# vitor-project.net
KiCad netlist of a schematic drawn in Altium Designer
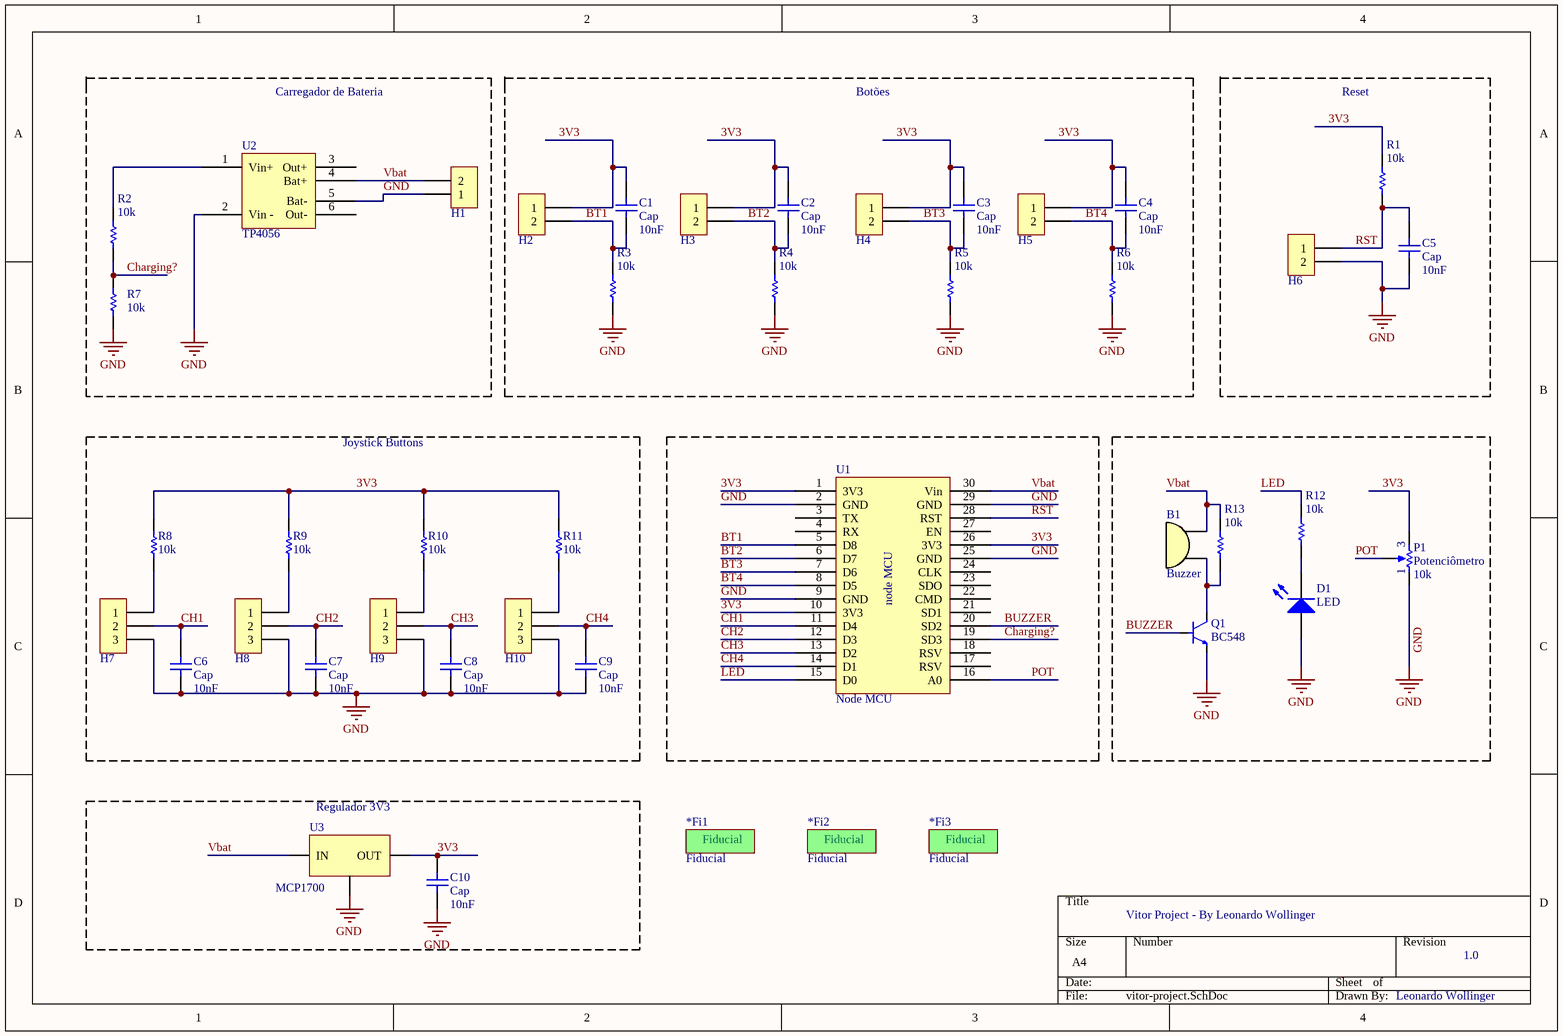
[diagram p0: vitor-project.SchDoc]

(export (version "E")
  (design (tool "Eeschema 10.0.6"))
  (components
    (comp (ref "*Fi1")
      (value "Fiducial")
      (footprint "Fiducial")
      (description "Fiduciais para montagem em pick n' place")
      (libsource (lib "pako") (part "Fiducial"))
    )
    (comp (ref "*Fi2")
      (value "Fiducial")
      (footprint "Fiducial")
      (description "Fiduciais para montagem em pick n' place")
      (libsource (lib "pako") (part "Fiducial"))
    )
    (comp (ref "*Fi3")
      (value "Fiducial")
      (footprint "Fiducial")
      (description "Fiduciais para montagem em pick n' place")
      (libsource (lib "pako") (part "Fiducial"))
    )
    (comp (ref "B1") (value "Buzzer") (footprint "Buzzer") (libsource (lib "pako") (part "Buzzer")))
    (comp (ref "C1")
      (value "Cap")
      (footprint "Cap 100")
      (fields (field (name "VALOR") "10nF"))
      (libsource (lib "pako") (part "Cap"))
    )
    (comp (ref "C2")
      (value "Cap")
      (footprint "Cap 100")
      (fields (field (name "VALOR") "10nF"))
      (libsource (lib "pako") (part "Cap"))
    )
    (comp (ref "C3")
      (value "Cap")
      (footprint "Cap 100")
      (fields (field (name "VALOR") "10nF"))
      (libsource (lib "pako") (part "Cap"))
    )
    (comp (ref "C4")
      (value "Cap")
      (footprint "Cap 100")
      (fields (field (name "VALOR") "10nF"))
      (libsource (lib "pako") (part "Cap"))
    )
    (comp (ref "C5")
      (value "Cap")
      (footprint "Cap 100")
      (fields (field (name "VALOR") "10nF"))
      (libsource (lib "pako") (part "Cap"))
    )
    (comp (ref "C6")
      (value "Cap")
      (footprint "Cap 100")
      (fields (field (name "VALOR") "10nF"))
      (libsource (lib "pako") (part "Cap"))
    )
    (comp (ref "C7")
      (value "Cap")
      (footprint "Cap 100")
      (fields (field (name "VALOR") "10nF"))
      (libsource (lib "pako") (part "Cap"))
    )
    (comp (ref "C8")
      (value "Cap")
      (footprint "Cap 100")
      (fields (field (name "VALOR") "10nF"))
      (libsource (lib "pako") (part "Cap"))
    )
    (comp (ref "C9")
      (value "Cap")
      (footprint "Cap 100")
      (fields (field (name "VALOR") "10nF"))
      (libsource (lib "pako") (part "Cap"))
    )
    (comp (ref "C10")
      (value "Cap")
      (footprint "Cap 100")
      (fields (field (name "VALOR") "10nF"))
      (libsource (lib "pako") (part "Cap"))
    )
    (comp (ref "D1") (value "LED") (footprint "LED 5mm") (libsource (lib "pako") (part "LED")))
    (comp (ref "H1")
      (value "Header 2x1")
      (footprint "Header 2x1")
      (libsource (lib "pako") (part "Header 2x1"))
    )
    (comp (ref "H2") (value "Header 2x1") (footprint "Header 2x1") (libsource (lib "") (part "Header 2x1_1")))
    (comp (ref "H3") (value "Header 2x1") (footprint "Header 2x1") (libsource (lib "") (part "Header 2x1_1")))
    (comp (ref "H4") (value "Header 2x1") (footprint "Header 2x1") (libsource (lib "") (part "Header 2x1_1")))
    (comp (ref "H5") (value "Header 2x1") (footprint "Header 2x1") (libsource (lib "") (part "Header 2x1_1")))
    (comp (ref "H6") (value "Header 2x1") (footprint "Header 2x1") (libsource (lib "") (part "Header 2x1_1")))
    (comp (ref "H7")
      (value "Header 3x1")
      (footprint "Header 3x1")
      (libsource (lib "pako") (part "Header 3x1"))
    )
    (comp (ref "H8")
      (value "Header 3x1")
      (footprint "Header 3x1")
      (libsource (lib "pako") (part "Header 3x1"))
    )
    (comp (ref "H9")
      (value "Header 3x1")
      (footprint "Header 3x1")
      (libsource (lib "pako") (part "Header 3x1"))
    )
    (comp (ref "H10")
      (value "Header 3x1")
      (footprint "Header 3x1")
      (libsource (lib "pako") (part "Header 3x1"))
    )
    (comp (ref "P1")
      (value "Potenciômetro")
      (footprint "Potenciometro Vertical")
      (fields (field (name "VALOR") "10k"))
      (libsource (lib "pako") (part "Potenciômetro"))
    )
    (comp (ref "Q1")
      (value "BC548")
      (footprint "TO-92")
      (description "Transistor NPN")
      (libsource (lib "pako") (part "BC548"))
    )
    (comp (ref "R1")
      (value "Resistor")
      (footprint "Resistor 1/4W")
      (fields (field (name "VALOR") "10k"))
      (libsource (lib "pako") (part "Resistor"))
    )
    (comp (ref "R2")
      (value "Resistor")
      (footprint "Resistor 1/4W")
      (fields (field (name "VALOR") "10k"))
      (libsource (lib "pako") (part "Resistor"))
    )
    (comp (ref "R3")
      (value "Resistor")
      (footprint "Resistor 1/4W")
      (fields (field (name "VALOR") "10k"))
      (libsource (lib "pako") (part "Resistor"))
    )
    (comp (ref "R4")
      (value "Resistor")
      (footprint "Resistor 1/4W")
      (fields (field (name "VALOR") "10k"))
      (libsource (lib "pako") (part "Resistor"))
    )
    (comp (ref "R5")
      (value "Resistor")
      (footprint "Resistor 1/4W")
      (fields (field (name "VALOR") "10k"))
      (libsource (lib "pako") (part "Resistor"))
    )
    (comp (ref "R6")
      (value "Resistor")
      (footprint "Resistor 1/4W")
      (fields (field (name "VALOR") "10k"))
      (libsource (lib "pako") (part "Resistor"))
    )
    (comp (ref "R7")
      (value "Resistor")
      (footprint "Resistor 1/4W")
      (fields (field (name "VALOR") "10k"))
      (libsource (lib "pako") (part "Resistor"))
    )
    (comp (ref "R8")
      (value "Resistor")
      (footprint "Resistor 1/4W")
      (fields (field (name "VALOR") "10k"))
      (libsource (lib "pako") (part "Resistor"))
    )
    (comp (ref "R9")
      (value "Resistor")
      (footprint "Resistor 1/4W")
      (fields (field (name "VALOR") "10k"))
      (libsource (lib "pako") (part "Resistor"))
    )
    (comp (ref "R10")
      (value "Resistor")
      (footprint "Resistor 1/4W")
      (fields (field (name "VALOR") "10k"))
      (libsource (lib "pako") (part "Resistor"))
    )
    (comp (ref "R11")
      (value "Resistor")
      (footprint "Resistor 1/4W")
      (fields (field (name "VALOR") "10k"))
      (libsource (lib "pako") (part "Resistor"))
    )
    (comp (ref "R12")
      (value "Resistor")
      (footprint "Resistor 1/4W")
      (fields (field (name "VALOR") "10k"))
      (libsource (lib "pako") (part "Resistor"))
    )
    (comp (ref "R13")
      (value "Resistor")
      (footprint "Resistor 1/4W")
      (fields (field (name "VALOR") "10k"))
      (libsource (lib "pako") (part "Resistor"))
    )
    (comp (ref "U1")
      (value "Node MCU")
      (footprint "pako:Node MCU")
      (libsource (lib "pako") (part "Node MCU"))
    )
    (comp (ref "U2") (value "TP4056") (footprint "pako:TP4056") (libsource (lib "pako") (part "TP4056")))
    (comp (ref "U3")
      (value "MCP1700")
      (footprint "TO-92")
      (description "LDO Voltage Regulator")
      (libsource (lib "pako") (part "MCP1700"))
    )
  )
  (nets
    (net (code "1") (name "/3V3") (class "Default")
      (node (ref "C1") (pin "1") (pintype "passive"))
      (node (ref "C10") (pin "1") (pintype "passive"))
      (node (ref "C2") (pin "1") (pintype "passive"))
      (node (ref "C3") (pin "1") (pintype "passive"))
      (node (ref "C4") (pin "1") (pintype "passive"))
      (node (ref "H2") (pin "1") (pinfunction "1_1") (pintype "passive"))
      (node (ref "H3") (pin "1") (pinfunction "1_1") (pintype "passive"))
      (node (ref "H4") (pin "1") (pinfunction "1_1") (pintype "passive"))
      (node (ref "H5") (pin "1") (pinfunction "1_1") (pintype "passive"))
      (node (ref "P1") (pin "3") (pinfunction "C_3") (pintype "passive"))
      (node (ref "R1") (pin "2") (pinfunction "2_2") (pintype "passive"))
      (node (ref "R10") (pin "2") (pinfunction "2_2") (pintype "passive"))
      (node (ref "R11") (pin "2") (pinfunction "2_2") (pintype "passive"))
      (node (ref "R8") (pin "2") (pinfunction "2_2") (pintype "passive"))
      (node (ref "R9") (pin "2") (pinfunction "2_2") (pintype "passive"))
      (node (ref "U1") (pin "1") (pinfunction "3V3_1") (pintype "passive"))
      (node (ref "U1") (pin "10") (pinfunction "3V3_10") (pintype "passive"))
      (node (ref "U1") (pin "26") (pinfunction "3V3_26") (pintype "passive"))
      (node (ref "U3") (pin "3") (pinfunction "OUT_3") (pintype "passive"))
    )
    (net (code "2") (name "/BT1") (class "Default")
      (node (ref "C1") (pin "2") (pintype "passive"))
      (node (ref "H2") (pin "2") (pinfunction "2_2") (pintype "passive"))
      (node (ref "R3") (pin "2") (pinfunction "2_2") (pintype "passive"))
      (node (ref "U1") (pin "5") (pinfunction "D8_5") (pintype "passive"))
    )
    (net (code "3") (name "/BT2") (class "Default")
      (node (ref "C2") (pin "2") (pintype "passive"))
      (node (ref "H3") (pin "2") (pinfunction "2_2") (pintype "passive"))
      (node (ref "R4") (pin "2") (pinfunction "2_2") (pintype "passive"))
      (node (ref "U1") (pin "6") (pinfunction "D7_6") (pintype "passive"))
    )
    (net (code "4") (name "/BT3") (class "Default")
      (node (ref "C3") (pin "2") (pintype "passive"))
      (node (ref "H4") (pin "2") (pinfunction "2_2") (pintype "passive"))
      (node (ref "R5") (pin "2") (pinfunction "2_2") (pintype "passive"))
      (node (ref "U1") (pin "7") (pinfunction "D6_7") (pintype "passive"))
    )
    (net (code "5") (name "/BT4") (class "Default")
      (node (ref "C4") (pin "2") (pintype "passive"))
      (node (ref "H5") (pin "2") (pinfunction "2_2") (pintype "passive"))
      (node (ref "R6") (pin "2") (pinfunction "2_2") (pintype "passive"))
      (node (ref "U1") (pin "8") (pinfunction "D5_8") (pintype "passive"))
    )
    (net (code "6") (name "/BUZZER") (class "Default")
      (node (ref "Q1") (pin "2") (pinfunction "B_2") (pintype "passive"))
      (node (ref "U1") (pin "20") (pinfunction "SD2_20") (pintype "passive"))
    )
    (net (code "7") (name "/CH1") (class "Default")
      (node (ref "C6") (pin "1") (pintype "passive"))
      (node (ref "H7") (pin "2") (pinfunction "2_2") (pintype "passive"))
      (node (ref "U1") (pin "11") (pinfunction "D4_11") (pintype "passive"))
    )
    (net (code "8") (name "/CH2") (class "Default")
      (node (ref "C7") (pin "1") (pintype "passive"))
      (node (ref "H8") (pin "2") (pinfunction "2_2") (pintype "passive"))
      (node (ref "U1") (pin "12") (pinfunction "D3_12") (pintype "passive"))
    )
    (net (code "9") (name "/CH3") (class "Default")
      (node (ref "C8") (pin "1") (pintype "passive"))
      (node (ref "H9") (pin "2") (pinfunction "2_2") (pintype "passive"))
      (node (ref "U1") (pin "13") (pinfunction "D2_13") (pintype "passive"))
    )
    (net (code "10") (name "/CH4") (class "Default")
      (node (ref "C9") (pin "1") (pintype "passive"))
      (node (ref "H10") (pin "2") (pinfunction "2_2") (pintype "passive"))
      (node (ref "U1") (pin "14") (pinfunction "D1_14") (pintype "passive"))
    )
    (net (code "11") (name "/Charging?") (class "Default")
      (node (ref "R2") (pin "1") (pinfunction "1_1") (pintype "passive"))
      (node (ref "R7") (pin "2") (pinfunction "2_2") (pintype "passive"))
      (node (ref "U1") (pin "19") (pinfunction "SD3_19") (pintype "passive"))
    )
    (net (code "12") (name "/LED") (class "Default")
      (node (ref "R12") (pin "2") (pinfunction "2_2") (pintype "passive"))
      (node (ref "U1") (pin "15") (pinfunction "D0_15") (pintype "passive"))
    )
    (net (code "13") (name "/POT") (class "Default")
      (node (ref "P1") (pin "2") (pinfunction "B_2") (pintype "passive"))
      (node (ref "U1") (pin "16") (pinfunction "A0_16") (pintype "passive"))
    )
    (net (code "14") (name "/RST") (class "Default")
      (node (ref "C5") (pin "1") (pintype "passive"))
      (node (ref "H6") (pin "1") (pinfunction "1_1") (pintype "passive"))
      (node (ref "R1") (pin "1") (pinfunction "1_1") (pintype "passive"))
      (node (ref "U1") (pin "28") (pinfunction "RST_28") (pintype "passive"))
    )
    (net (code "15") (name "/Vbat") (class "Default")
      (node (ref "B1") (pin "2") (pinfunction "-_2") (pintype "passive"))
      (node (ref "H1") (pin "2") (pinfunction "2_2") (pintype "passive"))
      (node (ref "R13") (pin "2") (pinfunction "2_2") (pintype "passive"))
      (node (ref "U1") (pin "30") (pinfunction "Vin_30") (pintype "passive"))
      (node (ref "U2") (pin "4") (pinfunction "Bat+_4") (pintype "passive"))
      (node (ref "U3") (pin "2") (pinfunction "IN_2") (pintype "passive"))
    )
    (net (code "16") (name "GND") (class "Default")
      (node (ref "C10") (pin "2") (pintype "passive"))
      (node (ref "C5") (pin "2") (pintype "passive"))
      (node (ref "C6") (pin "2") (pintype "passive"))
      (node (ref "C7") (pin "2") (pintype "passive"))
      (node (ref "C8") (pin "2") (pintype "passive"))
      (node (ref "C9") (pin "2") (pintype "passive"))
      (node (ref "D1") (pin "1") (pinfunction "A_1") (pintype "passive"))
      (node (ref "H1") (pin "1") (pinfunction "1_1") (pintype "passive"))
      (node (ref "H10") (pin "3") (pinfunction "3_3") (pintype "passive"))
      (node (ref "H6") (pin "2") (pinfunction "2_2") (pintype "passive"))
      (node (ref "H7") (pin "3") (pinfunction "3_3") (pintype "passive"))
      (node (ref "H8") (pin "3") (pinfunction "3_3") (pintype "passive"))
      (node (ref "H9") (pin "3") (pinfunction "3_3") (pintype "passive"))
      (node (ref "P1") (pin "1") (pinfunction "A_1") (pintype "passive"))
      (node (ref "Q1") (pin "3") (pinfunction "E_3") (pintype "passive"))
      (node (ref "R3") (pin "1") (pinfunction "1_1") (pintype "passive"))
      (node (ref "R4") (pin "1") (pinfunction "1_1") (pintype "passive"))
      (node (ref "R5") (pin "1") (pinfunction "1_1") (pintype "passive"))
      (node (ref "R6") (pin "1") (pinfunction "1_1") (pintype "passive"))
      (node (ref "R7") (pin "1") (pinfunction "1_1") (pintype "passive"))
      (node (ref "U1") (pin "2") (pinfunction "GND_2") (pintype "passive"))
      (node (ref "U1") (pin "25") (pinfunction "GND_25") (pintype "passive"))
      (node (ref "U1") (pin "29") (pinfunction "GND_29") (pintype "passive"))
      (node (ref "U1") (pin "9") (pinfunction "GND_9") (pintype "passive"))
      (node (ref "U2") (pin "2") (pinfunction "Vin_-_2") (pintype "passive"))
      (node (ref "U2") (pin "5") (pinfunction "Bat-_5") (pintype "passive"))
      (node (ref "U3") (pin "1") (pinfunction "GND_1") (pintype "passive"))
    )
    (net (code "17") (name "Net-(B1-+)") (class "Default")
      (node (ref "B1") (pin "1") (pinfunction "+_1") (pintype "passive"))
      (node (ref "Q1") (pin "1") (pinfunction "C_1") (pintype "passive"))
      (node (ref "R13") (pin "1") (pinfunction "1_1") (pintype "passive"))
    )
    (net (code "18") (name "Net-(D1-K)") (class "Default")
      (node (ref "D1") (pin "2") (pinfunction "K_2") (pintype "passive"))
      (node (ref "R12") (pin "1") (pinfunction "1_1") (pintype "passive"))
    )
    (net (code "19") (name "Net-(H7-Pad1)") (class "Default")
      (node (ref "H7") (pin "1") (pinfunction "1_1") (pintype "passive"))
      (node (ref "R8") (pin "1") (pinfunction "1_1") (pintype "passive"))
    )
    (net (code "20") (name "Net-(H8-Pad1)") (class "Default")
      (node (ref "H8") (pin "1") (pinfunction "1_1") (pintype "passive"))
      (node (ref "R9") (pin "1") (pinfunction "1_1") (pintype "passive"))
    )
    (net (code "21") (name "Net-(H9-Pad1)") (class "Default")
      (node (ref "H9") (pin "1") (pinfunction "1_1") (pintype "passive"))
      (node (ref "R10") (pin "1") (pinfunction "1_1") (pintype "passive"))
    )
    (net (code "22") (name "Net-(H10-Pad1)") (class "Default")
      (node (ref "H10") (pin "1") (pinfunction "1_1") (pintype "passive"))
      (node (ref "R11") (pin "1") (pinfunction "1_1") (pintype "passive"))
    )
    (net (code "23") (name "Net-(U2-Vin+)") (class "Default")
      (node (ref "R2") (pin "2") (pinfunction "2_2") (pintype "passive"))
      (node (ref "U2") (pin "1") (pinfunction "Vin+_1") (pintype "passive"))
    )
    (net (code "24") (name "unconnected-(U1-CLK-Pad24)") (class "Default")
      (node (ref "U1") (pin "24") (pinfunction "CLK_24") (pintype "passive"))
    )
    (net (code "25") (name "unconnected-(U1-CMD-Pad22)") (class "Default")
      (node (ref "U1") (pin "22") (pinfunction "CMD_22") (pintype "passive"))
    )
    (net (code "26") (name "unconnected-(U1-EN-Pad27)") (class "Default")
      (node (ref "U1") (pin "27") (pinfunction "EN_27") (pintype "passive"))
    )
    (net (code "27") (name "unconnected-(U1-RSV-Pad17)") (class "Default")
      (node (ref "U1") (pin "17") (pinfunction "RSV_17") (pintype "passive"))
    )
    (net (code "28") (name "unconnected-(U1-RSV-Pad18)") (class "Default")
      (node (ref "U1") (pin "18") (pinfunction "RSV_18") (pintype "passive"))
    )
    (net (code "29") (name "unconnected-(U1-RX-Pad4)") (class "Default")
      (node (ref "U1") (pin "4") (pinfunction "RX_4") (pintype "passive"))
    )
    (net (code "30") (name "unconnected-(U1-SD1-Pad21)") (class "Default")
      (node (ref "U1") (pin "21") (pinfunction "SD1_21") (pintype "passive"))
    )
    (net (code "31") (name "unconnected-(U1-SDO-Pad23)") (class "Default")
      (node (ref "U1") (pin "23") (pinfunction "SDO_23") (pintype "passive"))
    )
    (net (code "32") (name "unconnected-(U1-TX-Pad3)") (class "Default")
      (node (ref "U1") (pin "3") (pinfunction "TX_3") (pintype "passive"))
    )
    (net (code "33") (name "unconnected-(U2-Out+-Pad3)") (class "Default")
      (node (ref "U2") (pin "3") (pinfunction "Out+_3") (pintype "passive"))
    )
    (net (code "34") (name "unconnected-(U2-Out--Pad6)") (class "Default")
      (node (ref "U2") (pin "6") (pinfunction "Out-_6") (pintype "passive"))
    )
  )
)
